# Bteam_Mother.net
KiCad netlist of a schematic drawn in EAGLE
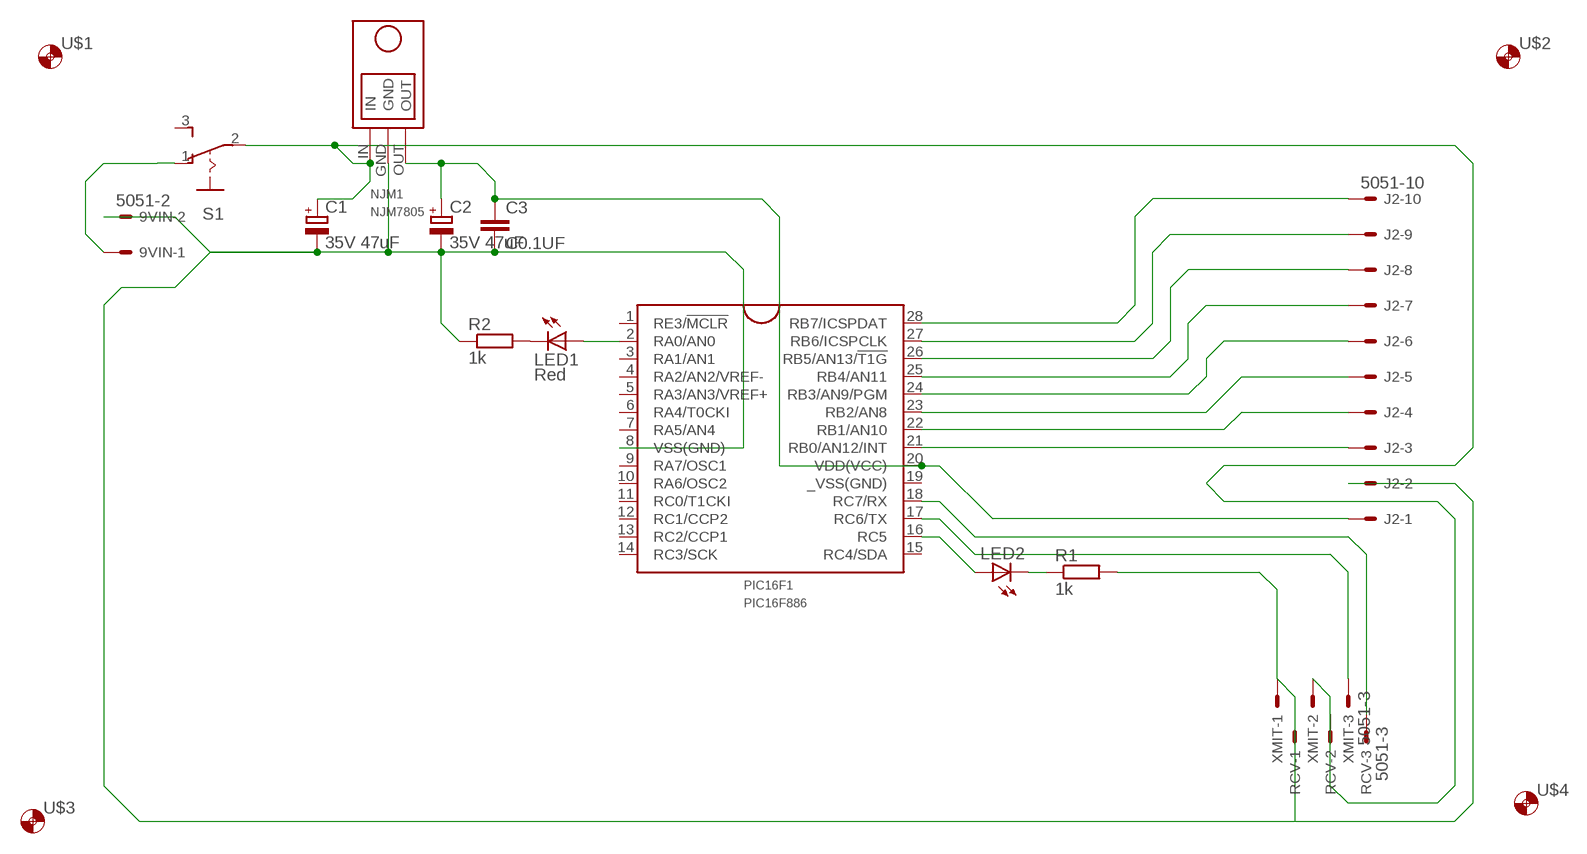
[diagram p0: schematic, sheet 1]

(export (version "E")
  (design (tool "Eeschema 10.0.6"))
  (components
    (comp (ref "9VIN")
      (value "5051-2")
      (footprint "eagle-import:2PL")
      (libsource (lib "eagle-import") (part "5051-2"))
    )
    (comp (ref "C1")
      (value "35V 47uF")
      (footprint "eagle-import:E2-5")
      (libsource (lib "eagle-import") (part "CPOL-EU2-5MM"))
    )
    (comp (ref "C2")
      (value "35V 47uF")
      (footprint "eagle-import:E2-5")
      (libsource (lib "eagle-import") (part "CPOL-EU2-5MM"))
    )
    (comp (ref "C3")
      (value "C0.1UF")
      (footprint "eagle-import:C0.1UF")
      (libsource (lib "eagle-import") (part "C0.1UF"))
    )
    (comp (ref "J2")
      (value "5051-10")
      (footprint "eagle-import:10PL")
      (libsource (lib "eagle-import") (part "5051-10"))
    )
    (comp (ref "LED1")
      (value "Red")
      (footprint "eagle-import:LED5MM")
      (libsource (lib "eagle-import") (part "LED5MM"))
    )
    (comp (ref "LED2")
      (value "LED5MM")
      (footprint "eagle-import:LED5MM")
      (libsource (lib "eagle-import") (part "LED5MM"))
    )
    (comp (ref "NJM1")
      (value "NJM7805")
      (footprint "eagle-import:NJM7805")
      (libsource (lib "eagle-import") (part "NJM7805"))
    )
    (comp (ref "PIC16F1")
      (value "PIC16F886")
      (footprint "eagle-import:DIL28-3")
      (libsource (lib "eagle-import") (part "PIC16F886"))
    )
    (comp (ref "R1")
      (value "1k")
      (footprint "eagle-import:0207_10")
      (libsource (lib "eagle-import") (part "R-EU2R0207/10"))
    )
    (comp (ref "R2")
      (value "1k")
      (footprint "eagle-import:0207_10")
      (libsource (lib "eagle-import") (part "R-EU2R0207/10"))
    )
    (comp (ref "RCV")
      (value "5051-3")
      (footprint "eagle-import:3PL")
      (libsource (lib "eagle-import") (part "5051-3"))
    )
    (comp (ref "S1")
      (value "SLIDESW")
      (footprint "eagle-import:SLIDESW")
      (libsource (lib "eagle-import") (part "SLIDESW"))
    )
    (comp (ref "U$1")
      (value "1MMDRILL")
      (footprint "eagle-import:1MDRILL")
      (libsource (lib "eagle-import") (part "1MMDRILL"))
    )
    (comp (ref "U$2")
      (value "1MMDRILL")
      (footprint "eagle-import:1MDRILL")
      (libsource (lib "eagle-import") (part "1MMDRILL"))
    )
    (comp (ref "U$3")
      (value "1MMDRILL")
      (footprint "eagle-import:1MDRILL")
      (libsource (lib "eagle-import") (part "1MMDRILL"))
    )
    (comp (ref "U$4")
      (value "1MMDRILL")
      (footprint "eagle-import:1MDRILL")
      (libsource (lib "eagle-import") (part "1MMDRILL"))
    )
    (comp (ref "XMIT")
      (value "5051-3")
      (footprint "eagle-import:3PL")
      (libsource (lib "eagle-import") (part "5051-3"))
    )
  )
  (nets
    (net (code "1") (name "/_VSS(GND)") (class "Default")
      (node (ref "PIC16F1") (pin "19") (pinfunction "_VSS(GND)_19") (pintype "power_in"))
    )
    (net (code "2") (name "Net-(9VINA-S)") (class "Default")
      (node (ref "9VIN") (pin "1") (pinfunction "S_1") (pintype "passive"))
      (node (ref "S1") (pin "1") (pinfunction "1_1") (pintype "passive"))
    )
    (net (code "3") (name "Net-(9VINB-S)") (class "Default")
      (node (ref "9VIN") (pin "2") (pinfunction "S_2") (pintype "passive"))
      (node (ref "C1") (pin "-") (pinfunction "-_-") (pintype "passive"))
      (node (ref "C2") (pin "-") (pinfunction "-_-") (pintype "passive"))
      (node (ref "C3") (pin "2") (pinfunction "2_2") (pintype "passive"))
      (node (ref "J2") (pin "2") (pinfunction "S_2") (pintype "passive"))
      (node (ref "NJM1") (pin "GND") (pinfunction "GND_GND") (pintype "bidirectional"))
      (node (ref "PIC16F1") (pin "8") (pinfunction "VSS(GND)_8") (pintype "power_in"))
      (node (ref "R1") (pin "2") (pinfunction "2_2") (pintype "passive"))
      (node (ref "R2") (pin "1") (pinfunction "1_1") (pintype "passive"))
      (node (ref "RCV") (pin "1") (pinfunction "S_1") (pintype "passive"))
      (node (ref "XMIT") (pin "1") (pinfunction "S_1") (pintype "passive"))
    )
    (net (code "4") (name "Net-(J2A-S)") (class "Default")
      (node (ref "C2") (pin "+") (pinfunction "+_+") (pintype "passive"))
      (node (ref "C3") (pin "1") (pinfunction "1_1") (pintype "passive"))
      (node (ref "J2") (pin "1") (pinfunction "S_1") (pintype "passive"))
      (node (ref "NJM1") (pin "OUT") (pinfunction "OUT_OUT") (pintype "bidirectional"))
      (node (ref "PIC16F1") (pin "20") (pinfunction "VDD(VCC)_20") (pintype "power_in"))
    )
    (net (code "5") (name "Net-(J2B-S)") (class "Default")
      (node (ref "J2") (pin "10") (pinfunction "S_10") (pintype "passive"))
      (node (ref "PIC16F1") (pin "28") (pinfunction "RB7/ICSPDAT_28") (pintype "bidirectional"))
    )
    (net (code "6") (name "Net-(J2D-S)") (class "Default")
      (node (ref "J2") (pin "3") (pinfunction "S_3") (pintype "passive"))
      (node (ref "PIC16F1") (pin "21") (pinfunction "RB0/AN12/INT_21") (pintype "bidirectional"))
    )
    (net (code "7") (name "Net-(J2E-S)") (class "Default")
      (node (ref "J2") (pin "4") (pinfunction "S_4") (pintype "passive"))
      (node (ref "PIC16F1") (pin "22") (pinfunction "RB1/AN10_22") (pintype "bidirectional"))
    )
    (net (code "8") (name "Net-(J2F-S)") (class "Default")
      (node (ref "J2") (pin "5") (pinfunction "S_5") (pintype "passive"))
      (node (ref "PIC16F1") (pin "23") (pinfunction "RB2/AN8_23") (pintype "bidirectional"))
    )
    (net (code "9") (name "Net-(J2G-S)") (class "Default")
      (node (ref "J2") (pin "6") (pinfunction "S_6") (pintype "passive"))
      (node (ref "PIC16F1") (pin "24") (pinfunction "RB3/AN9/PGM_24") (pintype "bidirectional"))
    )
    (net (code "10") (name "Net-(J2H-S)") (class "Default")
      (node (ref "J2") (pin "7") (pinfunction "S_7") (pintype "passive"))
      (node (ref "PIC16F1") (pin "25") (pinfunction "RB4/AN11_25") (pintype "bidirectional"))
    )
    (net (code "11") (name "Net-(J2I-S)") (class "Default")
      (node (ref "J2") (pin "8") (pinfunction "S_8") (pintype "passive"))
      (node (ref "PIC16F1") (pin "26") (pinfunction "RB5/AN13/~{T1G}_26") (pintype "bidirectional"))
    )
    (net (code "12") (name "Net-(J2J-S)") (class "Default")
      (node (ref "J2") (pin "9") (pinfunction "S_9") (pintype "passive"))
      (node (ref "PIC16F1") (pin "27") (pinfunction "RB6/ICSPCLK_27") (pintype "bidirectional"))
    )
    (net (code "13") (name "Net-(LED1-C)") (class "Default")
      (node (ref "LED1") (pin "K") (pinfunction "C_K") (pintype "passive"))
      (node (ref "R2") (pin "2") (pinfunction "2_2") (pintype "passive"))
    )
    (net (code "14") (name "Net-(LED2-C)") (class "Default")
      (node (ref "LED2") (pin "K") (pinfunction "C_K") (pintype "passive"))
      (node (ref "R1") (pin "1") (pinfunction "1_1") (pintype "passive"))
    )
    (net (code "15") (name "Net-(PIC16F1-RA0{slash}AN0)") (class "Default")
      (node (ref "LED1") (pin "A") (pinfunction "A_A") (pintype "passive"))
      (node (ref "PIC16F1") (pin "2") (pinfunction "RA0/AN0_2") (pintype "bidirectional"))
    )
    (net (code "16") (name "Net-(PIC16F1-RC5)") (class "Default")
      (node (ref "LED2") (pin "A") (pinfunction "A_A") (pintype "passive"))
      (node (ref "PIC16F1") (pin "16") (pinfunction "RC5_16") (pintype "bidirectional"))
    )
    (net (code "17") (name "Net-(PIC16F1-RC6{slash}TX)") (class "Default")
      (node (ref "PIC16F1") (pin "17") (pinfunction "RC6/TX_17") (pintype "bidirectional"))
      (node (ref "XMIT") (pin "3") (pinfunction "S_3") (pintype "passive"))
    )
    (net (code "18") (name "Net-(PIC16F1-RC7{slash}RX)") (class "Default")
      (node (ref "PIC16F1") (pin "18") (pinfunction "RC7/RX_18") (pintype "bidirectional"))
      (node (ref "RCV") (pin "3") (pinfunction "S_3") (pintype "passive"))
    )
    (net (code "19") (name "Net-(RCVB-S)") (class "Default")
      (node (ref "C1") (pin "+") (pinfunction "+_+") (pintype "passive"))
      (node (ref "NJM1") (pin "IN") (pinfunction "IN_IN") (pintype "bidirectional"))
      (node (ref "RCV") (pin "2") (pinfunction "S_2") (pintype "passive"))
      (node (ref "S1") (pin "2") (pinfunction "2_2") (pintype "passive"))
      (node (ref "XMIT") (pin "2") (pinfunction "S_2") (pintype "passive"))
    )
    (net (code "20") (name "unconnected-(PIC16F1-RA1{slash}AN1-Pad3)") (class "Default")
      (node (ref "PIC16F1") (pin "3") (pinfunction "RA1/AN1_3") (pintype "bidirectional"))
    )
    (net (code "21") (name "unconnected-(PIC16F1-RA2{slash}AN2{slash}VREF--Pad4)") (class "Default")
      (node (ref "PIC16F1") (pin "4") (pinfunction "RA2/AN2/VREF-_4") (pintype "bidirectional"))
    )
    (net (code "22") (name "unconnected-(PIC16F1-RA3{slash}AN3{slash}VREF+-Pad5)") (class "Default")
      (node (ref "PIC16F1") (pin "5") (pinfunction "RA3/AN3/VREF+_5") (pintype "bidirectional"))
    )
    (net (code "23") (name "unconnected-(PIC16F1-RA4{slash}T0CKI-Pad6)") (class "Default")
      (node (ref "PIC16F1") (pin "6") (pinfunction "RA4/T0CKI_6") (pintype "bidirectional"))
    )
    (net (code "24") (name "unconnected-(PIC16F1-RA5{slash}AN4-Pad7)") (class "Default")
      (node (ref "PIC16F1") (pin "7") (pinfunction "RA5/AN4_7") (pintype "bidirectional"))
    )
    (net (code "25") (name "unconnected-(PIC16F1-RA6{slash}OSC2-Pad10)") (class "Default")
      (node (ref "PIC16F1") (pin "10") (pinfunction "RA6/OSC2_10") (pintype "bidirectional"))
    )
    (net (code "26") (name "unconnected-(PIC16F1-RA7{slash}OSC1-Pad9)") (class "Default")
      (node (ref "PIC16F1") (pin "9") (pinfunction "RA7/OSC1_9") (pintype "bidirectional"))
    )
    (net (code "27") (name "unconnected-(PIC16F1-RC0{slash}T1CKI-Pad11)") (class "Default")
      (node (ref "PIC16F1") (pin "11") (pinfunction "RC0/T1CKI_11") (pintype "bidirectional"))
    )
    (net (code "28") (name "unconnected-(PIC16F1-RC1{slash}CCP2-Pad12)") (class "Default")
      (node (ref "PIC16F1") (pin "12") (pinfunction "RC1/CCP2_12") (pintype "bidirectional"))
    )
    (net (code "29") (name "unconnected-(PIC16F1-RC2{slash}CCP1-Pad13)") (class "Default")
      (node (ref "PIC16F1") (pin "13") (pinfunction "RC2/CCP1_13") (pintype "bidirectional"))
    )
    (net (code "30") (name "unconnected-(PIC16F1-RC3{slash}SCK-Pad14)") (class "Default")
      (node (ref "PIC16F1") (pin "14") (pinfunction "RC3/SCK_14") (pintype "bidirectional"))
    )
    (net (code "31") (name "unconnected-(PIC16F1-RC4{slash}SDA-Pad15)") (class "Default")
      (node (ref "PIC16F1") (pin "15") (pinfunction "RC4/SDA_15") (pintype "bidirectional"))
    )
    (net (code "32") (name "unconnected-(PIC16F1-RE3{slash}~{MCLR}-Pad1)") (class "Default")
      (node (ref "PIC16F1") (pin "1") (pinfunction "RE3/~{MCLR}_1") (pintype "bidirectional"))
    )
    (net (code "33") (name "unconnected-(S1-Pad3)") (class "Default")
      (node (ref "S1") (pin "3") (pinfunction "3_3") (pintype "passive"))
    )
  )
)
